# Protoboard.net
KiCad netlist of a schematic drawn in Altium Designer
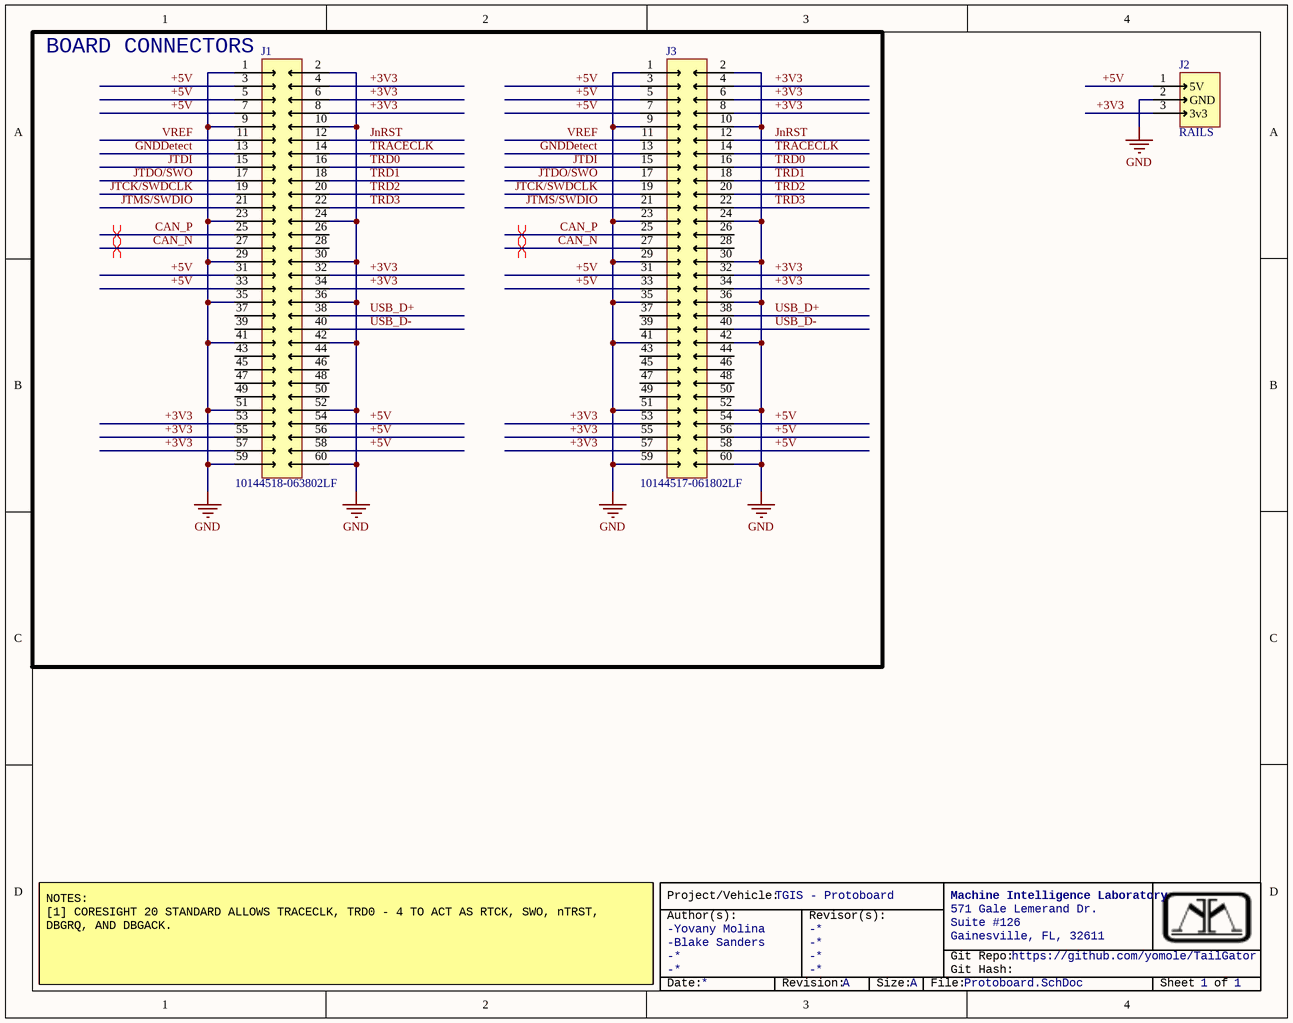
[diagram p0: Protoboard.SchDoc]

(export (version "E")
  (design (tool "Eeschema 10.0.6"))
  (components
    (comp (ref "J1")
      (value "10144518-063802LF")
      (footprint "AMPHENOL_10144518-063802LF")
      (description "CONN PLUG 60POS SMD GOLD")
      (libsource (lib "TGIS_Connectors") (part "10144518-063802LF"))
    )
    (comp (ref "J2")
      (value "RAILS")
      (footprint "75x95VIAS")
      (libsource (lib "TGIS_Protoboard") (part "PROTORAIL1"))
    )
    (comp (ref "J3")
      (value "10144517-061802LF")
      (footprint "AMPHENOL_10144517-061802LF")
      (description "CONN RCPT 60POS SMD GOLD")
      (libsource (lib "TGIS_Connectors") (part "10144517-061802LF"))
    )
  )
  (nets
    (net (code "1") (name "/+3V3") (class "Default")
      (node (ref "J1") (pin "32") (pinfunction "32_32") (pintype "passive"))
      (node (ref "J1") (pin "34") (pinfunction "34_34") (pintype "passive"))
      (node (ref "J1") (pin "4") (pinfunction "4_4") (pintype "passive"))
      (node (ref "J1") (pin "53") (pinfunction "53_53") (pintype "passive"))
      (node (ref "J1") (pin "55") (pinfunction "55_55") (pintype "passive"))
      (node (ref "J1") (pin "57") (pinfunction "57_57") (pintype "passive"))
      (node (ref "J1") (pin "6") (pinfunction "6_6") (pintype "passive"))
      (node (ref "J1") (pin "8") (pinfunction "8_8") (pintype "passive"))
      (node (ref "J2") (pin "3") (pinfunction "3v3_3") (pintype "passive"))
      (node (ref "J3") (pin "32") (pinfunction "32_32") (pintype "passive"))
      (node (ref "J3") (pin "34") (pinfunction "34_34") (pintype "passive"))
      (node (ref "J3") (pin "4") (pinfunction "4_4") (pintype "passive"))
      (node (ref "J3") (pin "53") (pinfunction "53_53") (pintype "passive"))
      (node (ref "J3") (pin "55") (pinfunction "55_55") (pintype "passive"))
      (node (ref "J3") (pin "57") (pinfunction "57_57") (pintype "passive"))
      (node (ref "J3") (pin "6") (pinfunction "6_6") (pintype "passive"))
      (node (ref "J3") (pin "8") (pinfunction "8_8") (pintype "passive"))
    )
    (net (code "2") (name "/+5V") (class "Default")
      (node (ref "J1") (pin "3") (pinfunction "3_3") (pintype "passive"))
      (node (ref "J1") (pin "31") (pinfunction "31_31") (pintype "passive"))
      (node (ref "J1") (pin "33") (pinfunction "33_33") (pintype "passive"))
      (node (ref "J1") (pin "5") (pinfunction "5_5") (pintype "passive"))
      (node (ref "J1") (pin "54") (pinfunction "54_54") (pintype "passive"))
      (node (ref "J1") (pin "56") (pinfunction "56_56") (pintype "passive"))
      (node (ref "J1") (pin "58") (pinfunction "58_58") (pintype "passive"))
      (node (ref "J1") (pin "7") (pinfunction "7_7") (pintype "passive"))
      (node (ref "J2") (pin "1") (pinfunction "5V_1") (pintype "passive"))
      (node (ref "J3") (pin "3") (pinfunction "3_3") (pintype "passive"))
      (node (ref "J3") (pin "31") (pinfunction "31_31") (pintype "passive"))
      (node (ref "J3") (pin "33") (pinfunction "33_33") (pintype "passive"))
      (node (ref "J3") (pin "5") (pinfunction "5_5") (pintype "passive"))
      (node (ref "J3") (pin "54") (pinfunction "54_54") (pintype "passive"))
      (node (ref "J3") (pin "56") (pinfunction "56_56") (pintype "passive"))
      (node (ref "J3") (pin "58") (pinfunction "58_58") (pintype "passive"))
      (node (ref "J3") (pin "7") (pinfunction "7_7") (pintype "passive"))
    )
    (net (code "3") (name "/CAN_N") (class "Default")
      (node (ref "J1") (pin "27") (pinfunction "27_27") (pintype "passive"))
      (node (ref "J3") (pin "27") (pinfunction "27_27") (pintype "passive"))
    )
    (net (code "4") (name "/CAN_P") (class "Default")
      (node (ref "J1") (pin "25") (pinfunction "25_25") (pintype "passive"))
      (node (ref "J3") (pin "25") (pinfunction "25_25") (pintype "passive"))
    )
    (net (code "5") (name "/GNDDetect") (class "Default")
      (node (ref "J1") (pin "13") (pinfunction "13_13") (pintype "passive"))
      (node (ref "J3") (pin "13") (pinfunction "13_13") (pintype "passive"))
    )
    (net (code "6") (name "/JTCK{slash}SWDCLK") (class "Default")
      (node (ref "J1") (pin "19") (pinfunction "19_19") (pintype "passive"))
      (node (ref "J3") (pin "19") (pinfunction "19_19") (pintype "passive"))
    )
    (net (code "7") (name "/JTDI") (class "Default")
      (node (ref "J1") (pin "15") (pinfunction "15_15") (pintype "passive"))
      (node (ref "J3") (pin "15") (pinfunction "15_15") (pintype "passive"))
    )
    (net (code "8") (name "/JTDO{slash}SWO") (class "Default")
      (node (ref "J1") (pin "17") (pinfunction "17_17") (pintype "passive"))
      (node (ref "J3") (pin "17") (pinfunction "17_17") (pintype "passive"))
    )
    (net (code "9") (name "/JTMS{slash}SWDIO") (class "Default")
      (node (ref "J1") (pin "21") (pinfunction "21_21") (pintype "passive"))
      (node (ref "J3") (pin "21") (pinfunction "21_21") (pintype "passive"))
    )
    (net (code "10") (name "/JnRST") (class "Default")
      (node (ref "J1") (pin "12") (pinfunction "12_12") (pintype "passive"))
      (node (ref "J3") (pin "12") (pinfunction "12_12") (pintype "passive"))
    )
    (net (code "11") (name "/TRACECLK") (class "Default")
      (node (ref "J1") (pin "14") (pinfunction "14_14") (pintype "passive"))
      (node (ref "J3") (pin "14") (pinfunction "14_14") (pintype "passive"))
    )
    (net (code "12") (name "/TRD0") (class "Default")
      (node (ref "J1") (pin "16") (pinfunction "16_16") (pintype "passive"))
      (node (ref "J3") (pin "16") (pinfunction "16_16") (pintype "passive"))
    )
    (net (code "13") (name "/TRD1") (class "Default")
      (node (ref "J1") (pin "18") (pinfunction "18_18") (pintype "passive"))
      (node (ref "J3") (pin "18") (pinfunction "18_18") (pintype "passive"))
    )
    (net (code "14") (name "/TRD2") (class "Default")
      (node (ref "J1") (pin "20") (pinfunction "20_20") (pintype "passive"))
      (node (ref "J3") (pin "20") (pinfunction "20_20") (pintype "passive"))
    )
    (net (code "15") (name "/TRD3") (class "Default")
      (node (ref "J1") (pin "22") (pinfunction "22_22") (pintype "passive"))
      (node (ref "J3") (pin "22") (pinfunction "22_22") (pintype "passive"))
    )
    (net (code "16") (name "/USB_D+") (class "Default")
      (node (ref "J1") (pin "38") (pinfunction "38_38") (pintype "passive"))
      (node (ref "J3") (pin "38") (pinfunction "38_38") (pintype "passive"))
    )
    (net (code "17") (name "/USB_D-") (class "Default")
      (node (ref "J1") (pin "40") (pinfunction "40_40") (pintype "passive"))
      (node (ref "J3") (pin "40") (pinfunction "40_40") (pintype "passive"))
    )
    (net (code "18") (name "/VREF") (class "Default")
      (node (ref "J1") (pin "11") (pinfunction "11_11") (pintype "passive"))
      (node (ref "J3") (pin "11") (pinfunction "11_11") (pintype "passive"))
    )
    (net (code "19") (name "GND") (class "Default")
      (node (ref "J1") (pin "1") (pinfunction "1_1") (pintype "passive"))
      (node (ref "J1") (pin "10") (pinfunction "10_10") (pintype "passive"))
      (node (ref "J1") (pin "2") (pinfunction "2_2") (pintype "passive"))
      (node (ref "J1") (pin "23") (pinfunction "23_23") (pintype "passive"))
      (node (ref "J1") (pin "24") (pinfunction "24_24") (pintype "passive"))
      (node (ref "J1") (pin "29") (pinfunction "29_29") (pintype "passive"))
      (node (ref "J1") (pin "30") (pinfunction "30_30") (pintype "passive"))
      (node (ref "J1") (pin "35") (pinfunction "35_35") (pintype "passive"))
      (node (ref "J1") (pin "36") (pinfunction "36_36") (pintype "passive"))
      (node (ref "J1") (pin "41") (pinfunction "41_41") (pintype "passive"))
      (node (ref "J1") (pin "42") (pinfunction "42_42") (pintype "passive"))
      (node (ref "J1") (pin "51") (pinfunction "51_51") (pintype "passive"))
      (node (ref "J1") (pin "52") (pinfunction "52_52") (pintype "passive"))
      (node (ref "J1") (pin "59") (pinfunction "59_59") (pintype "passive"))
      (node (ref "J1") (pin "60") (pinfunction "60_60") (pintype "passive"))
      (node (ref "J1") (pin "9") (pinfunction "9_9") (pintype "passive"))
      (node (ref "J2") (pin "2") (pinfunction "GND_2") (pintype "passive"))
      (node (ref "J3") (pin "1") (pinfunction "1_1") (pintype "passive"))
      (node (ref "J3") (pin "10") (pinfunction "10_10") (pintype "passive"))
      (node (ref "J3") (pin "2") (pinfunction "2_2") (pintype "passive"))
      (node (ref "J3") (pin "23") (pinfunction "23_23") (pintype "passive"))
      (node (ref "J3") (pin "24") (pinfunction "24_24") (pintype "passive"))
      (node (ref "J3") (pin "29") (pinfunction "29_29") (pintype "passive"))
      (node (ref "J3") (pin "30") (pinfunction "30_30") (pintype "passive"))
      (node (ref "J3") (pin "35") (pinfunction "35_35") (pintype "passive"))
      (node (ref "J3") (pin "36") (pinfunction "36_36") (pintype "passive"))
      (node (ref "J3") (pin "41") (pinfunction "41_41") (pintype "passive"))
      (node (ref "J3") (pin "42") (pinfunction "42_42") (pintype "passive"))
      (node (ref "J3") (pin "51") (pinfunction "51_51") (pintype "passive"))
      (node (ref "J3") (pin "52") (pinfunction "52_52") (pintype "passive"))
      (node (ref "J3") (pin "59") (pinfunction "59_59") (pintype "passive"))
      (node (ref "J3") (pin "60") (pinfunction "60_60") (pintype "passive"))
      (node (ref "J3") (pin "9") (pinfunction "9_9") (pintype "passive"))
    )
    (net (code "20") (name "unconnected-(J1-Pad26)") (class "Default")
      (node (ref "J1") (pin "26") (pinfunction "26_26") (pintype "passive"))
    )
    (net (code "21") (name "unconnected-(J1-Pad28)") (class "Default")
      (node (ref "J1") (pin "28") (pinfunction "28_28") (pintype "passive"))
    )
    (net (code "22") (name "unconnected-(J1-Pad37)") (class "Default")
      (node (ref "J1") (pin "37") (pinfunction "37_37") (pintype "passive"))
    )
    (net (code "23") (name "unconnected-(J1-Pad39)") (class "Default")
      (node (ref "J1") (pin "39") (pinfunction "39_39") (pintype "passive"))
    )
    (net (code "24") (name "unconnected-(J1-Pad43)") (class "Default")
      (node (ref "J1") (pin "43") (pinfunction "43_43") (pintype "passive"))
    )
    (net (code "25") (name "unconnected-(J1-Pad44)") (class "Default")
      (node (ref "J1") (pin "44") (pinfunction "44_44") (pintype "passive"))
    )
    (net (code "26") (name "unconnected-(J1-Pad45)") (class "Default")
      (node (ref "J1") (pin "45") (pinfunction "45_45") (pintype "passive"))
    )
    (net (code "27") (name "unconnected-(J1-Pad46)") (class "Default")
      (node (ref "J1") (pin "46") (pinfunction "46_46") (pintype "passive"))
    )
    (net (code "28") (name "unconnected-(J1-Pad47)") (class "Default")
      (node (ref "J1") (pin "47") (pinfunction "47_47") (pintype "passive"))
    )
    (net (code "29") (name "unconnected-(J1-Pad48)") (class "Default")
      (node (ref "J1") (pin "48") (pinfunction "48_48") (pintype "passive"))
    )
    (net (code "30") (name "unconnected-(J1-Pad49)") (class "Default")
      (node (ref "J1") (pin "49") (pinfunction "49_49") (pintype "passive"))
    )
    (net (code "31") (name "unconnected-(J1-Pad50)") (class "Default")
      (node (ref "J1") (pin "50") (pinfunction "50_50") (pintype "passive"))
    )
    (net (code "32") (name "unconnected-(J3-Pad26)") (class "Default")
      (node (ref "J3") (pin "26") (pinfunction "26_26") (pintype "passive"))
    )
    (net (code "33") (name "unconnected-(J3-Pad28)") (class "Default")
      (node (ref "J3") (pin "28") (pinfunction "28_28") (pintype "passive"))
    )
    (net (code "34") (name "unconnected-(J3-Pad37)") (class "Default")
      (node (ref "J3") (pin "37") (pinfunction "37_37") (pintype "passive"))
    )
    (net (code "35") (name "unconnected-(J3-Pad39)") (class "Default")
      (node (ref "J3") (pin "39") (pinfunction "39_39") (pintype "passive"))
    )
    (net (code "36") (name "unconnected-(J3-Pad43)") (class "Default")
      (node (ref "J3") (pin "43") (pinfunction "43_43") (pintype "passive"))
    )
    (net (code "37") (name "unconnected-(J3-Pad44)") (class "Default")
      (node (ref "J3") (pin "44") (pinfunction "44_44") (pintype "passive"))
    )
    (net (code "38") (name "unconnected-(J3-Pad45)") (class "Default")
      (node (ref "J3") (pin "45") (pinfunction "45_45") (pintype "passive"))
    )
    (net (code "39") (name "unconnected-(J3-Pad46)") (class "Default")
      (node (ref "J3") (pin "46") (pinfunction "46_46") (pintype "passive"))
    )
    (net (code "40") (name "unconnected-(J3-Pad47)") (class "Default")
      (node (ref "J3") (pin "47") (pinfunction "47_47") (pintype "passive"))
    )
    (net (code "41") (name "unconnected-(J3-Pad48)") (class "Default")
      (node (ref "J3") (pin "48") (pinfunction "48_48") (pintype "passive"))
    )
    (net (code "42") (name "unconnected-(J3-Pad49)") (class "Default")
      (node (ref "J3") (pin "49") (pinfunction "49_49") (pintype "passive"))
    )
    (net (code "43") (name "unconnected-(J3-Pad50)") (class "Default")
      (node (ref "J3") (pin "50") (pinfunction "50_50") (pintype "passive"))
    )
  )
)
